# plp-cbot_2a.net
KiCad netlist of a schematic drawn in Altium Designer
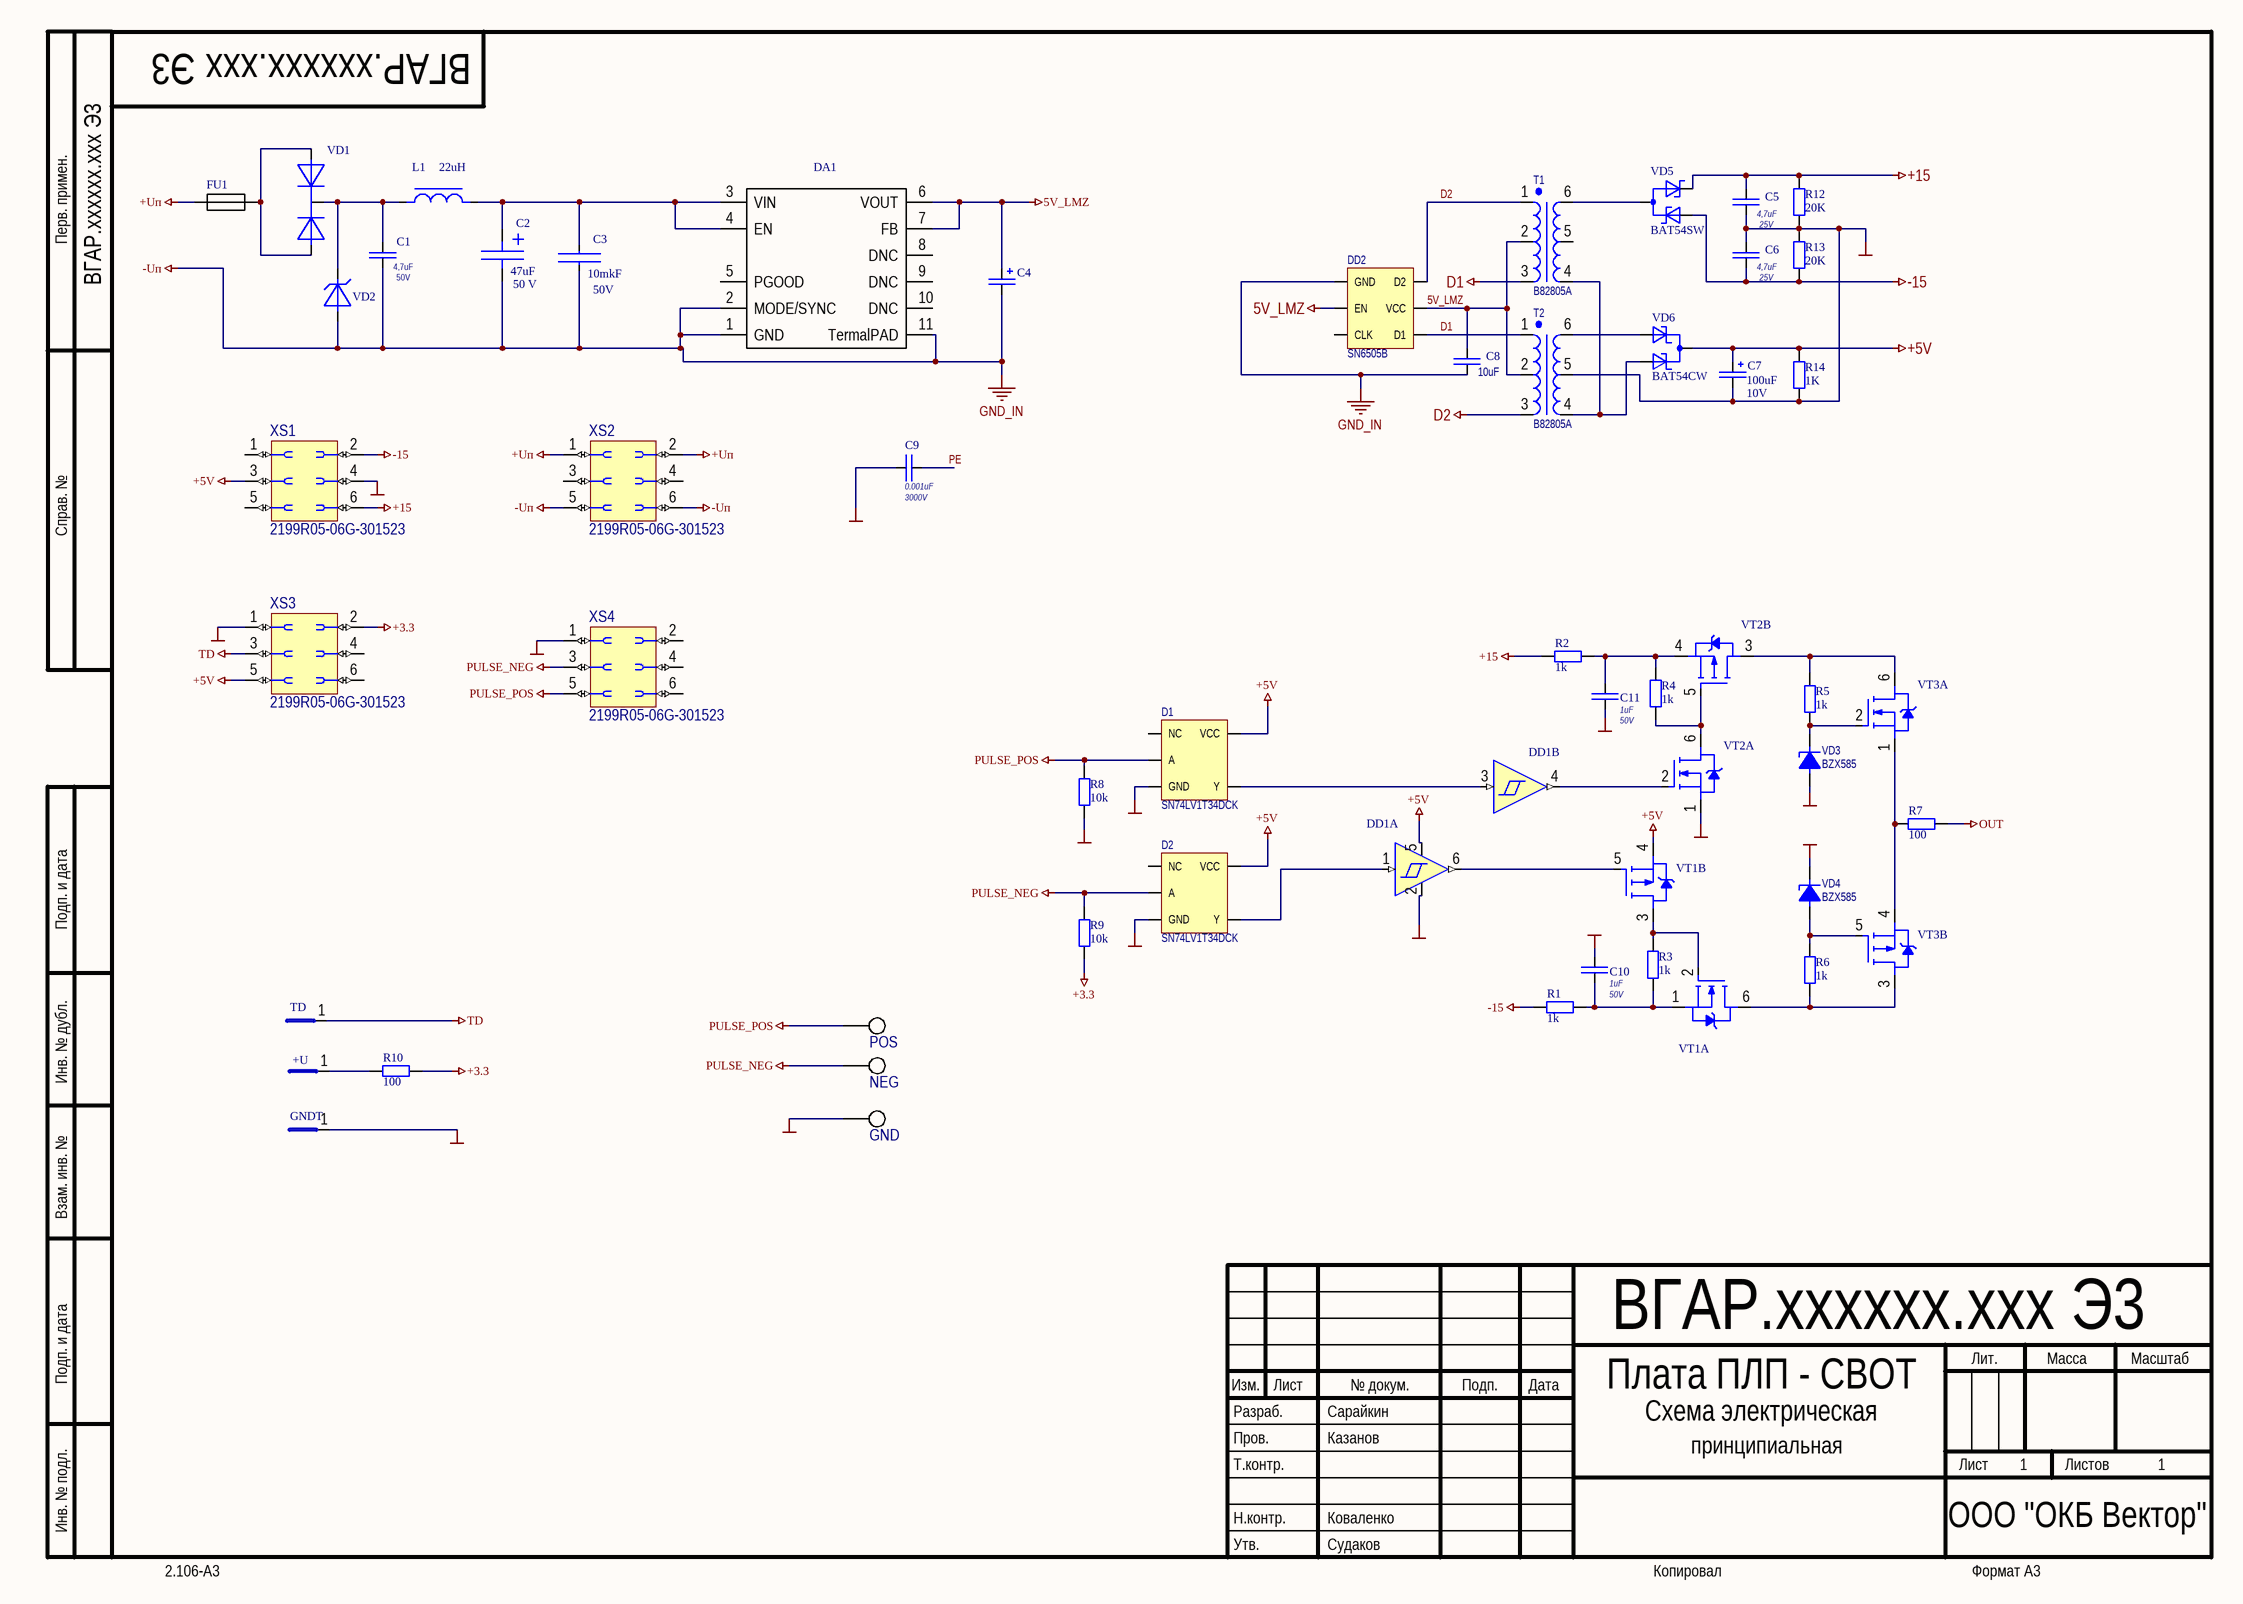
[diagram p0: plp-cbot_2a.SchDoc]

(export (version "E")
  (design (tool "Eeschema 10.0.6"))
  (components
    (comp (ref "+U")
      (value "smd_pin")
      (footprint "smd_pin")
      (libsource (lib "Board Level Debug Tools") (part "smd_pin"))
    )
    (comp (ref "C1")
      (value "4,7uF")
      (footprint "CAPC_0603(1608)X080L")
      (description "Конденсатор")
      (fields
        (field (name "MANUFACTURER") "Murata")
        (field (name "TOLERANCE") "±10%")
        (field (name "RATED DC VOLTAGE") "50V")
      )
      (libsource (lib "Chip Capacitor") (part "Capacitor Ceramic"))
    )
    (comp (ref "C2")
      (value "47uF")
      (footprint "CAPSM_D_M7878X54L")
      (description "Конденсатор")
      (fields
        (field (name "MANUFACTURER") "Panasonic")
        (field (name "TOLERANCE") "±20%")
        (field (name "RATED DC VOLTAGE") "50 V")
      )
      (libsource (lib "Panasonic Capacitor") (part "SMD 5.3XD6.3 ALUM 22uFx50V"))
    )
    (comp (ref "C3")
      (value "10mkF")
      (footprint "CAPC_1210(3225)X10L")
      (description "Capacitor Chip")
      (fields (field (name "ALTIUM_UNNAMED_1") "50V") (field (name "Comment") "CAPC_1210(3225)X10"))
      (libsource (lib "Yageo Chip Capacitor") (part "CAPC_1210(3225)X10"))
    )
    (comp (ref "C4")
      (value "~")
      (footprint "CAP_B3528X21N")
      (description "Конденсатор")
      (fields (field (name "MANUFACTURER") "Murata"))
      (libsource (lib "Chip Capacitor") (part "Capacitor Polarized"))
    )
    (comp (ref "C5")
      (value "4,7uF")
      (footprint "CAPC_0603(1608)X080L")
      (description "Конденсатор")
      (fields
        (field (name "MANUFACTURER") "Murata")
        (field (name "TOLERANCE") "±10%")
        (field (name "RATED DC VOLTAGE") "25V")
      )
      (libsource (lib "Chip Capacitor") (part "Capacitor Ceramic"))
    )
    (comp (ref "C6")
      (value "4,7uF")
      (footprint "CAPC_0603(1608)X080L")
      (description "Конденсатор")
      (fields
        (field (name "MANUFACTURER") "Murata")
        (field (name "TOLERANCE") "±10%")
        (field (name "RATED DC VOLTAGE") "25V")
      )
      (libsource (lib "Chip Capacitor") (part "Capacitor Ceramic"))
    )
    (comp (ref "C7")
      (value "100uF")
      (footprint "CAP_B3528X21N")
      (description "Конденсатор")
      (fields (field (name "MANUFACTURER") "Murata") (field (name "RATED DC VOLTAGE") "10V"))
      (libsource (lib "Chip Capacitor") (part "Capacitor Polarized"))
    )
    (comp (ref "C8")
      (value "10uF")
      (footprint "CAPC_0603(1608)X080L")
      (description "Конденсатор")
      (fields (field (name "MANUFACTURER") "Murata") (field (name "TOLERANCE") "±10%"))
      (libsource (lib "Chip Capacitor") (part "Capacitor Ceramic"))
    )
    (comp (ref "C9")
      (value "0.001uF")
      (footprint "CAPC_1812(4532)X16L")
      (description "Конденсатор")
      (fields
        (field (name "MANUFACTURER") "Murata")
        (field (name "PARTNUMBER") "0603 - 0,1 мкФ ± 10 % - 50 В - X7R")
        (field (name "RATED DC VOLTAGE") "3000V")
      )
      (libsource (lib "Chip Capacitor") (part "Capacitor Ceramic"))
    )
    (comp (ref "C10")
      (value "1uF")
      (footprint "CAPC_0603(1608)X080L")
      (description "Конденсатор")
      (fields
        (field (name "MANUFACTURER") "Murata")
        (field (name "PARTNUMBER") "GRM188R71C105KA12D - 0603 - 1 мкФ ± 10 % - 16 В - X7R")
        (field (name "RATED DC VOLTAGE") "50V")
      )
      (libsource (lib "Chip Capacitor") (part "0603 - X7R - 16V - 1uF"))
    )
    (comp (ref "C11")
      (value "1uF")
      (footprint "CAPC_0603(1608)X080L")
      (description "Конденсатор")
      (fields
        (field (name "MANUFACTURER") "Murata")
        (field (name "PARTNUMBER") "GRM188R71C105KA12D - 0603 - 1 мкФ ± 10 % - 16 В - X7R")
        (field (name "RATED DC VOLTAGE") "50V")
      )
      (libsource (lib "Chip Capacitor") (part "0603 - X7R - 16V - 1uF"))
    )
    (comp (ref "D1")
      (value "SN74LV1T34DCK")
      (footprint "SC70-5")
      (description "Single Buffer")
      (libsource (lib "ic-logic") (part "SN74LV1T34DCK"))
    )
    (comp (ref "D2")
      (value "SN74LV1T34DCK")
      (footprint "SC70-5")
      (description "Single Buffer")
      (libsource (lib "ic-logic") (part "SN74LV1T34DCK"))
    )
    (comp (ref "DA1")
      (value "LMZM23600")
      (footprint "MicroSIP")
      (description "Микросхема")
      (fields (field (name "MANUFACTURER") "Texas Instruments"))
      (libsource (lib "TI Power Mgt Switchmode Regulator") (part "LMZM23600"))
    )
    (comp (ref "DD1")
      (value "NC7WZ17P6X")
      (footprint "SC-70-6")
      (description "UHS Dual Buffer with Schmitt Trigger Inputs")
      (libsource (lib "Fairchild Logic") (part "NC7WZ17P6X"))
    )
    (comp (ref "DD2")
      (value "SN6505B")
      (footprint "SOT23-6")
      (description "Low-Noise 1-A Transformer Drivers for Isolated Power Supplies")
      (libsource (lib "ic-power-module") (part "SN6505A"))
    )
    (comp (ref "FU1")
      (value "MF-MSMF")
      (footprint "FU4532(1812)X06N")
      (description "Самовостанавливающийся предохранитель")
      (fields (field (name "MANUFACTURER") "Bourns") (field (name "PARTNUMBER") "MF-MSMF 010/60-2"))
      (libsource (lib "Bourns Chip Fuse") (part "MF-MSMF"))
    )
    (comp (ref "GND")
      (value "Testpoint_HS1mm")
      (footprint "TestPoint(1mm_HS)")
      (libsource (lib "connector") (part "Testpoint_HS1mm"))
    )
    (comp (ref "GNDT")
      (value "smd_pin")
      (footprint "smd_pin")
      (libsource (lib "Board Level Debug Tools") (part "smd_pin"))
    )
    (comp (ref "L1")
      (value "22uH")
      (footprint "CDRH4D28_INDP5050X28N")
      (fields (field (name "Comment") "CDRH4D28"))
      (libsource (lib "Sumida Power Inductor") (part "CDRH4D28"))
    )
    (comp (ref "NEG")
      (value "Testpoint_HS1mm")
      (footprint "TestPoint(1mm_HS)")
      (libsource (lib "connector") (part "Testpoint_HS1mm"))
    )
    (comp (ref "POS")
      (value "Testpoint_HS1mm")
      (footprint "TestPoint(1mm_HS)")
      (libsource (lib "connector") (part "Testpoint_HS1mm"))
    )
    (comp (ref "R1")
      (value "1k")
      (footprint "RESC1608(0603)X04L")
      (description "Резистор")
      (fields (field (name "MANUFACTURER") "Bourns") (field (name "POWER") "1/10 Вт"))
      (libsource (lib "") (part "R0603L_2"))
    )
    (comp (ref "R2")
      (value "1k")
      (footprint "RESC1608(0603)X04L")
      (description "Резистор")
      (fields (field (name "MANUFACTURER") "Bourns") (field (name "POWER") "1/10 Вт"))
      (libsource (lib "") (part "R0603L_2"))
    )
    (comp (ref "R3")
      (value "1k")
      (footprint "RESC1608(0603)X04L")
      (description "Резистор")
      (fields (field (name "MANUFACTURER") "Bourns") (field (name "POWER") "1/10 Вт"))
      (libsource (lib "") (part "R0603L_1"))
    )
    (comp (ref "R4")
      (value "1k")
      (footprint "RESC1608(0603)X04L")
      (description "Резистор")
      (fields (field (name "MANUFACTURER") "Bourns") (field (name "POWER") "1/10 Вт"))
      (libsource (lib "") (part "R0603L_1"))
    )
    (comp (ref "R5")
      (value "1k")
      (footprint "RESC1608(0603)X04L")
      (description "Резистор")
      (fields (field (name "MANUFACTURER") "Bourns") (field (name "POWER") "1/10 Вт"))
      (libsource (lib "Chip Resistor") (part "R0603L"))
    )
    (comp (ref "R6")
      (value "1k")
      (footprint "RESC1608(0603)X04L")
      (description "Резистор")
      (fields (field (name "MANUFACTURER") "Bourns") (field (name "POWER") "1/10 Вт"))
      (libsource (lib "Chip Resistor") (part "R0603L"))
    )
    (comp (ref "R7")
      (value "100")
      (footprint "RESC1608(0603)X04L")
      (description "Резистор")
      (fields (field (name "MANUFACTURER") "Bourns") (field (name "POWER") "1/10 Вт"))
      (libsource (lib "") (part "R0603L_3"))
    )
    (comp (ref "R8")
      (value "10k")
      (footprint "RESC1608(0603)X04L")
      (description "Резистор")
      (fields (field (name "MANUFACTURER") "Bourns") (field (name "POWER") "1/10 Вт"))
      (libsource (lib "") (part "R0603L_1"))
    )
    (comp (ref "R9")
      (value "10k")
      (footprint "RESC1608(0603)X04L")
      (description "Резистор")
      (fields (field (name "MANUFACTURER") "Bourns") (field (name "POWER") "1/10 Вт"))
      (libsource (lib "") (part "R0603L_1"))
    )
    (comp (ref "R10")
      (value "100")
      (footprint "RESC1608(0603)X04L")
      (description "Резистор")
      (fields (field (name "MANUFACTURER") "Bourns") (field (name "POWER") "1/10 Вт"))
      (libsource (lib "") (part "R0603L_3"))
    )
    (comp (ref "R12")
      (value "20K")
      (footprint "RESC1608(0603)X04L")
      (description "Резистор")
      (fields (field (name "MANUFACTURER") "Bourns") (field (name "POWER") "1/10 Вт"))
      (libsource (lib "") (part "R0603L_1"))
    )
    (comp (ref "R13")
      (value "20K")
      (footprint "RESC1608(0603)X04L")
      (description "Резистор")
      (fields (field (name "MANUFACTURER") "Bourns") (field (name "POWER") "1/10 Вт"))
      (libsource (lib "") (part "R0603L_1"))
    )
    (comp (ref "R14")
      (value "1K")
      (footprint "RESC1608(0603)X04L")
      (description "Резистор")
      (fields (field (name "MANUFACTURER") "Bourns") (field (name "POWER") "1/10 Вт"))
      (libsource (lib "") (part "R0603L_1"))
    )
    (comp (ref "T1")
      (value "B82805A")
      (footprint "B82805A")
      (description "SMT Push-Pull Transformers")
      (libsource (lib "transformer") (part "B82805A"))
    )
    (comp (ref "T2")
      (value "B82805A")
      (footprint "B82805A")
      (description "SMT Push-Pull Transformers")
      (libsource (lib "transformer") (part "B82805A"))
    )
    (comp (ref "TD")
      (value "smd_pin")
      (footprint "smd_pin")
      (libsource (lib "Board Level Debug Tools") (part "smd_pin"))
    )
    (comp (ref "VD1")
      (value "BAV70W")
      (footprint "SC-70")
      (description "Сборка диодная")
      (fields (field (name "MANUFACTURER") "NXP"))
      (libsource (lib "NXP Diodes") (part "BAV70W"))
    )
    (comp (ref "VD2")
      (value "SMBJ33A")
      (footprint "SMB")
      (description "TVS Диод")
      (fields
        (field (name "REPLACEMENTPART1PARTNUMBER") "PTVS33VP1UP")
        (field (name "MANUFACTURER") "ST Microelectronics")
      )
      (libsource (lib "ST Protection Diodes") (part "SMBJ33A"))
    )
    (comp (ref "VD3")
      (value "BZX585")
      (footprint "DIODE: SOD523")
      (description "Voltage regulator diodes")
      (libsource (lib "diode") (part "BZX585"))
    )
    (comp (ref "VD4")
      (value "BZX585")
      (footprint "DIODE: SOD523")
      (description "Voltage regulator diodes")
      (libsource (lib "diode") (part "BZX585"))
    )
    (comp (ref "VD5")
      (value "BAT54SW")
      (footprint "SC-70")
      (description "Сборка диодная")
      (fields (field (name "MANUFACTURER") "NXP") (field (name "REPLACEMENTPART1PARTNUMBER") "BAT54SWT1G"))
      (libsource (lib "NXP Diodes") (part "BAT54SW"))
    )
    (comp (ref "VD6")
      (value "BAT54CW")
      (footprint "SC-70")
      (description "Сборка диодная")
      (fields (field (name "MANUFACTURER") "NXP") (field (name "REPLACEMENTPART1PARTNUMBER") "BAT54CWT1G"))
      (libsource (lib "NXP Diodes") (part "BAT54CW"))
    )
    (comp (ref "VT1")
      (value "NX3008CBKS")
      (footprint "SC-70-6")
      (description "Сборка транзисторная")
      (fields (field (name "MANUFACTURER") "Fairchild Semiconductor") (field (name "PARTNUMBER") "BSS84AKS"))
      (libsource (lib "NXP Transistors") (part "NX3008CBKS"))
    )
    (comp (ref "VT2")
      (value "NX3008CBKS")
      (footprint "SC-70-6")
      (description "Сборка транзисторная")
      (fields (field (name "MANUFACTURER") "Fairchild Semiconductor") (field (name "PARTNUMBER") "BSS84AKS"))
      (libsource (lib "NXP Transistors") (part "NX3008CBKS"))
    )
    (comp (ref "VT3")
      (value "NX3008CBKS")
      (footprint "SC-70-6")
      (description "Сборка транзисторная")
      (fields (field (name "MANUFACTURER") "Fairchild Semiconductor") (field (name "PARTNUMBER") "BSS84AKS"))
      (libsource (lib "NXP Transistors") (part "NX3008CBKS"))
    )
    (comp (ref "XS1")
      (value "2199R05-06G-301523")
      (footprint "CON: PLL-6(2x3R1.27female)")
      (description "Step 1.27")
      (libsource (lib "connector") (part "2199R05-06G-301523In"))
    )
    (comp (ref "XS2")
      (value "2199R05-06G-301523")
      (footprint "CON: PLL-6(2x3R1.27female)")
      (description "Step 1.27")
      (libsource (lib "connector") (part "2199R05-06G-301523In"))
    )
    (comp (ref "XS3")
      (value "2199R05-06G-301523")
      (footprint "CON: PLL-6(2x3R1.27female)")
      (description "Step 1.27")
      (libsource (lib "connector") (part "2199R05-06G-301523In"))
    )
    (comp (ref "XS4")
      (value "2199R05-06G-301523")
      (footprint "CON: PLL-6(2x3R1.27female)")
      (description "Step 1.27")
      (libsource (lib "connector") (part "2199R05-06G-301523In"))
    )
  )
  (nets
    (net (code "1") (name "+3.3") (class "Default")
      (node (ref "R10") (pin "2") (pinfunction "2_2") (pintype "passive"))
      (node (ref "R9") (pin "1") (pinfunction "1_1") (pintype "passive"))
      (node (ref "XS3") (pin "2") (pinfunction "2_2") (pintype "bidirectional"))
    )
    (net (code "2") (name "+5V") (class "Default")
      (node (ref "C7") (pin "1") (pinfunction "1_1") (pintype "passive"))
      (node (ref "D1") (pin "5") (pinfunction "VCC_5") (pintype "passive"))
      (node (ref "D2") (pin "5") (pinfunction "VCC_5") (pintype "passive"))
      (node (ref "DD1") (pin "5") (pinfunction "Vdd_5") (pintype "passive"))
      (node (ref "R14") (pin "2") (pinfunction "2_2") (pintype "passive"))
      (node (ref "VD6") (pin "3") (pinfunction "OC_3") (pintype "passive"))
      (node (ref "VT1") (pin "4") (pinfunction "S2_4") (pintype "passive"))
      (node (ref "XS1") (pin "3") (pinfunction "3_3") (pintype "bidirectional"))
      (node (ref "XS3") (pin "5") (pinfunction "5_5") (pintype "bidirectional"))
    )
    (net (code "3") (name "+15") (class "Default")
      (node (ref "C5") (pin "2") (pinfunction "2_2") (pintype "passive"))
      (node (ref "R12") (pin "2") (pinfunction "2_2") (pintype "passive"))
      (node (ref "R2") (pin "2") (pinfunction "2_2") (pintype "passive"))
      (node (ref "VD5") (pin "2") (pinfunction "C_2") (pintype "passive"))
      (node (ref "XS1") (pin "6") (pinfunction "6_6") (pintype "bidirectional"))
    )
    (net (code "4") (name "+Uп") (class "Default")
      (node (ref "FU1") (pin "1") (pinfunction "1_1") (pintype "passive"))
      (node (ref "XS2") (pin "1") (pinfunction "1_1") (pintype "bidirectional"))
      (node (ref "XS2") (pin "2") (pinfunction "2_2") (pintype "bidirectional"))
    )
    (net (code "5") (name "-15") (class "Default")
      (node (ref "C6") (pin "1") (pinfunction "1_1") (pintype "passive"))
      (node (ref "R1") (pin "2") (pinfunction "2_2") (pintype "passive"))
      (node (ref "R13") (pin "1") (pinfunction "1_1") (pintype "passive"))
      (node (ref "VD5") (pin "1") (pinfunction "A_1") (pintype "passive"))
      (node (ref "XS1") (pin "2") (pinfunction "2_2") (pintype "bidirectional"))
    )
    (net (code "6") (name "-Uп") (class "Default")
      (node (ref "C1") (pin "1") (pinfunction "1_1") (pintype "passive"))
      (node (ref "C2") (pin "2") (pinfunction "2_2") (pintype "passive"))
      (node (ref "C3") (pin "1") (pinfunction "1_1") (pintype "passive"))
      (node (ref "C4") (pin "2") (pinfunction "2_2") (pintype "passive"))
      (node (ref "C8") (pin "1") (pinfunction "1_1") (pintype "passive"))
      (node (ref "DA1") (pin "1") (pinfunction "GND_1") (pintype "passive"))
      (node (ref "DA1") (pin "11") (pinfunction "TermalPAD_11") (pintype "passive"))
      (node (ref "DA1") (pin "2") (pinfunction "MODE/SYNC_2") (pintype "passive"))
      (node (ref "DD2") (pin "4") (pinfunction "GND_4") (pintype "passive"))
      (node (ref "VD2") (pin "2") (pinfunction "A_2") (pintype "passive"))
      (node (ref "XS2") (pin "5") (pinfunction "5_5") (pintype "bidirectional"))
      (node (ref "XS2") (pin "6") (pinfunction "6_6") (pintype "bidirectional"))
    )
    (net (code "7") (name "/PE") (class "Default")
      (node (ref "C9") (pin "2") (pinfunction "2_2") (pintype "passive"))
    )
    (net (code "8") (name "5V_LMZ") (class "Default")
      (node (ref "C4") (pin "1") (pinfunction "1_1") (pintype "passive"))
      (node (ref "C8") (pin "2") (pinfunction "2_2") (pintype "passive"))
      (node (ref "DA1") (pin "6") (pinfunction "VOUT_6") (pintype "passive"))
      (node (ref "DA1") (pin "7") (pinfunction "FB_7") (pintype "passive"))
      (node (ref "DD2") (pin "2") (pinfunction "VCC_2") (pintype "passive"))
      (node (ref "DD2") (pin "5") (pinfunction "EN_5") (pintype "passive"))
      (node (ref "T1") (pin "2") (pinfunction "2_2") (pintype "passive"))
      (node (ref "T2") (pin "2") (pinfunction "2_2") (pintype "passive"))
    )
    (net (code "9") (name "D1") (class "Default")
      (node (ref "DD2") (pin "1") (pinfunction "D1_1") (pintype "passive"))
      (node (ref "T1") (pin "3") (pinfunction "3_3") (pintype "passive"))
      (node (ref "T2") (pin "1") (pinfunction "1_1") (pintype "passive"))
    )
    (net (code "10") (name "D2") (class "Default")
      (node (ref "DD2") (pin "3") (pinfunction "D2_3") (pintype "passive"))
      (node (ref "T1") (pin "1") (pinfunction "1_1") (pintype "passive"))
      (node (ref "T2") (pin "3") (pinfunction "3_3") (pintype "passive"))
    )
    (net (code "11") (name "GND") (class "Default")
      (node (ref "C10") (pin "2") (pinfunction "2_2") (pintype "passive"))
      (node (ref "C11") (pin "1") (pinfunction "1_1") (pintype "passive"))
      (node (ref "C5") (pin "1") (pinfunction "1_1") (pintype "passive"))
      (node (ref "C6") (pin "2") (pinfunction "2_2") (pintype "passive"))
      (node (ref "C7") (pin "2") (pinfunction "2_2") (pintype "passive"))
      (node (ref "C9") (pin "1") (pinfunction "1_1") (pintype "passive"))
      (node (ref "D1") (pin "3") (pinfunction "GND_3") (pintype "passive"))
      (node (ref "D2") (pin "3") (pinfunction "GND_3") (pintype "passive"))
      (node (ref "DD1") (pin "2") (pinfunction "GND_2") (pintype "passive"))
      (node (ref "GND") (pin "1") (pinfunction "1_1") (pintype "passive"))
      (node (ref "GNDT") (pin "1") (pinfunction "0_1") (pintype "passive"))
      (node (ref "R12") (pin "1") (pinfunction "1_1") (pintype "passive"))
      (node (ref "R13") (pin "2") (pinfunction "2_2") (pintype "passive"))
      (node (ref "R14") (pin "1") (pinfunction "1_1") (pintype "passive"))
      (node (ref "R8") (pin "1") (pinfunction "1_1") (pintype "passive"))
      (node (ref "T2") (pin "5") (pinfunction "5_5") (pintype "passive"))
      (node (ref "VD3") (pin "1") (pinfunction "2_1") (pintype "passive"))
      (node (ref "VD4") (pin "2") (pinfunction "1_2") (pintype "passive"))
      (node (ref "VT2") (pin "1") (pinfunction "S1_1") (pintype "passive"))
      (node (ref "XS1") (pin "4") (pinfunction "4_4") (pintype "bidirectional"))
      (node (ref "XS3") (pin "1") (pinfunction "1_1") (pintype "bidirectional"))
      (node (ref "XS4") (pin "1") (pinfunction "1_1") (pintype "bidirectional"))
    )
    (net (code "12") (name "Net-(+U-0)") (class "Default")
      (node (ref "+U") (pin "1") (pinfunction "0_1") (pintype "passive"))
      (node (ref "R10") (pin "1") (pinfunction "1_1") (pintype "passive"))
    )
    (net (code "13") (name "Net-(D1-Y)") (class "Default")
      (node (ref "D1") (pin "4") (pinfunction "Y_4") (pintype "passive"))
      (node (ref "DD1") (pin "3") (pinfunction "A2_3") (pintype "input"))
    )
    (net (code "14") (name "Net-(D2-Y)") (class "Default")
      (node (ref "D2") (pin "4") (pinfunction "Y_4") (pintype "passive"))
      (node (ref "DD1") (pin "1") (pinfunction "A1_1") (pintype "input"))
    )
    (net (code "15") (name "Net-(DA1-EN)") (class "Default")
      (node (ref "C2") (pin "1") (pinfunction "1_1") (pintype "passive"))
      (node (ref "C3") (pin "2") (pinfunction "2_2") (pintype "passive"))
      (node (ref "DA1") (pin "3") (pinfunction "VIN_3") (pintype "passive"))
      (node (ref "DA1") (pin "4") (pinfunction "EN_4") (pintype "passive"))
      (node (ref "L1") (pin "2") (pinfunction "2_2") (pintype "passive"))
    )
    (net (code "16") (name "Net-(DD1A-Y1)") (class "Default")
      (node (ref "DD1") (pin "6") (pinfunction "Y1_6") (pintype "output"))
      (node (ref "VT1") (pin "5") (pinfunction "G2_5") (pintype "passive"))
    )
    (net (code "17") (name "Net-(DD1B-Y2)") (class "Default")
      (node (ref "DD1") (pin "4") (pinfunction "Y2_4") (pintype "output"))
      (node (ref "VT2") (pin "2") (pinfunction "G1_2") (pintype "passive"))
    )
    (net (code "18") (name "Net-(FU1-Pad2)") (class "Default")
      (node (ref "FU1") (pin "2") (pinfunction "2_2") (pintype "passive"))
      (node (ref "VD1") (pin "1") (pinfunction "A_1") (pintype "passive"))
      (node (ref "VD1") (pin "2") (pinfunction "A_2") (pintype "passive"))
    )
    (net (code "19") (name "Net-(T1-Pad4)") (class "Default")
      (node (ref "T1") (pin "4") (pinfunction "4_4") (pintype "passive"))
      (node (ref "T2") (pin "4") (pinfunction "4_4") (pintype "passive"))
      (node (ref "VD6") (pin "2") (pinfunction "A_2") (pintype "passive"))
    )
    (net (code "20") (name "Net-(T2-Pad6)") (class "Default")
      (node (ref "T2") (pin "6") (pinfunction "6_6") (pintype "passive"))
      (node (ref "VD6") (pin "1") (pinfunction "A_1") (pintype "passive"))
    )
    (net (code "21") (name "Net-(VD1-OC)") (class "Default")
      (node (ref "C1") (pin "2") (pinfunction "2_2") (pintype "passive"))
      (node (ref "L1") (pin "1") (pinfunction "1_1") (pintype "passive"))
      (node (ref "VD1") (pin "3") (pinfunction "OC_3") (pintype "passive"))
      (node (ref "VD2") (pin "1") (pinfunction "C_1") (pintype "passive"))
    )
    (net (code "22") (name "Net-(VD3-1)") (class "Default")
      (node (ref "R5") (pin "2") (pinfunction "2_2") (pintype "passive"))
      (node (ref "VD3") (pin "2") (pinfunction "1_2") (pintype "passive"))
      (node (ref "VT3") (pin "2") (pinfunction "G1_2") (pintype "passive"))
    )
    (net (code "23") (name "Net-(VD4-2)") (class "Default")
      (node (ref "R6") (pin "1") (pinfunction "1_1") (pintype "passive"))
      (node (ref "VD4") (pin "1") (pinfunction "2_1") (pintype "passive"))
      (node (ref "VT3") (pin "5") (pinfunction "G2_5") (pintype "passive"))
    )
    (net (code "24") (name "Net-(VD5-OAC)") (class "Default")
      (node (ref "T1") (pin "6") (pinfunction "6_6") (pintype "passive"))
      (node (ref "VD5") (pin "3") (pinfunction "OAC_3") (pintype "passive"))
    )
    (net (code "25") (name "Net-(VT1A-D1)") (class "Default")
      (node (ref "R6") (pin "2") (pinfunction "2_2") (pintype "passive"))
      (node (ref "VT1") (pin "6") (pinfunction "D1_6") (pintype "passive"))
      (node (ref "VT3") (pin "3") (pinfunction "D2_3") (pintype "passive"))
    )
    (net (code "26") (name "Net-(VT1A-G1)") (class "Default")
      (node (ref "R3") (pin "2") (pinfunction "2_2") (pintype "passive"))
      (node (ref "VT1") (pin "2") (pinfunction "G1_2") (pintype "passive"))
      (node (ref "VT1") (pin "3") (pinfunction "D2_3") (pintype "passive"))
    )
    (net (code "27") (name "Net-(VT1A-S1)") (class "Default")
      (node (ref "C10") (pin "1") (pinfunction "1_1") (pintype "passive"))
      (node (ref "R1") (pin "1") (pinfunction "1_1") (pintype "passive"))
      (node (ref "R3") (pin "1") (pinfunction "1_1") (pintype "passive"))
      (node (ref "VT1") (pin "1") (pinfunction "S1_1") (pintype "passive"))
    )
    (net (code "28") (name "Net-(VT2A-D1)") (class "Default")
      (node (ref "R4") (pin "1") (pinfunction "1_1") (pintype "passive"))
      (node (ref "VT2") (pin "5") (pinfunction "G2_5") (pintype "passive"))
      (node (ref "VT2") (pin "6") (pinfunction "D1_6") (pintype "passive"))
    )
    (net (code "29") (name "Net-(VT2B-D2)") (class "Default")
      (node (ref "R5") (pin "1") (pinfunction "1_1") (pintype "passive"))
      (node (ref "VT2") (pin "3") (pinfunction "D2_3") (pintype "passive"))
      (node (ref "VT3") (pin "6") (pinfunction "D1_6") (pintype "passive"))
    )
    (net (code "30") (name "Net-(VT2B-S2)") (class "Default")
      (node (ref "C11") (pin "2") (pinfunction "2_2") (pintype "passive"))
      (node (ref "R2") (pin "1") (pinfunction "1_1") (pintype "passive"))
      (node (ref "R4") (pin "2") (pinfunction "2_2") (pintype "passive"))
      (node (ref "VT2") (pin "4") (pinfunction "S2_4") (pintype "passive"))
    )
    (net (code "31") (name "Net-(VT3A-S1)") (class "Default")
      (node (ref "R7") (pin "1") (pinfunction "1_1") (pintype "passive"))
      (node (ref "VT3") (pin "1") (pinfunction "S1_1") (pintype "passive"))
      (node (ref "VT3") (pin "4") (pinfunction "S2_4") (pintype "passive"))
    )
    (net (code "32") (name "OUT") (class "Default")
      (node (ref "R7") (pin "2") (pinfunction "2_2") (pintype "passive"))
    )
    (net (code "33") (name "PULSE_NEG") (class "Default")
      (node (ref "D2") (pin "2") (pinfunction "A_2") (pintype "passive"))
      (node (ref "NEG") (pin "1") (pinfunction "1_1") (pintype "passive"))
      (node (ref "R9") (pin "2") (pinfunction "2_2") (pintype "passive"))
      (node (ref "XS4") (pin "3") (pinfunction "3_3") (pintype "bidirectional"))
    )
    (net (code "34") (name "PULSE_POS") (class "Default")
      (node (ref "D1") (pin "2") (pinfunction "A_2") (pintype "passive"))
      (node (ref "POS") (pin "1") (pinfunction "1_1") (pintype "passive"))
      (node (ref "R8") (pin "2") (pinfunction "2_2") (pintype "passive"))
      (node (ref "XS4") (pin "5") (pinfunction "5_5") (pintype "bidirectional"))
    )
    (net (code "35") (name "TD") (class "Default")
      (node (ref "TD") (pin "1") (pinfunction "0_1") (pintype "passive"))
      (node (ref "XS3") (pin "3") (pinfunction "3_3") (pintype "bidirectional"))
    )
    (net (code "36") (name "unconnected-(D1-NC-Pad1)") (class "Default")
      (node (ref "D1") (pin "1") (pinfunction "NC_1") (pintype "passive"))
    )
    (net (code "37") (name "unconnected-(D2-NC-Pad1)") (class "Default")
      (node (ref "D2") (pin "1") (pinfunction "NC_1") (pintype "passive"))
    )
    (net (code "38") (name "unconnected-(DA1-DNC-Pad8)") (class "Default")
      (node (ref "DA1") (pin "8") (pinfunction "DNC_8") (pintype "passive"))
    )
    (net (code "39") (name "unconnected-(DA1-DNC-Pad9)") (class "Default")
      (node (ref "DA1") (pin "9") (pinfunction "DNC_9") (pintype "passive"))
    )
    (net (code "40") (name "unconnected-(DA1-DNC-Pad10)") (class "Default")
      (node (ref "DA1") (pin "10") (pinfunction "DNC_10") (pintype "passive"))
    )
    (net (code "41") (name "unconnected-(DA1-PGOOD-Pad5)") (class "Default")
      (node (ref "DA1") (pin "5") (pinfunction "PGOOD_5") (pintype "passive"))
    )
    (net (code "42") (name "unconnected-(DD2-CLK-Pad6)") (class "Default")
      (node (ref "DD2") (pin "6") (pinfunction "CLK_6") (pintype "passive"))
    )
    (net (code "43") (name "unconnected-(T1-Pad5)") (class "Default")
      (node (ref "T1") (pin "5") (pinfunction "5_5") (pintype "passive"))
    )
    (net (code "44") (name "unconnected-(XS1-Pad1)") (class "Default")
      (node (ref "XS1") (pin "1") (pinfunction "1_1") (pintype "bidirectional"))
    )
    (net (code "45") (name "unconnected-(XS1-Pad5)") (class "Default")
      (node (ref "XS1") (pin "5") (pinfunction "5_5") (pintype "bidirectional"))
    )
    (net (code "46") (name "unconnected-(XS2-Pad3)") (class "Default")
      (node (ref "XS2") (pin "3") (pinfunction "3_3") (pintype "bidirectional"))
    )
    (net (code "47") (name "unconnected-(XS2-Pad4)") (class "Default")
      (node (ref "XS2") (pin "4") (pinfunction "4_4") (pintype "bidirectional"))
    )
    (net (code "48") (name "unconnected-(XS3-Pad4)") (class "Default")
      (node (ref "XS3") (pin "4") (pinfunction "4_4") (pintype "bidirectional"))
    )
    (net (code "49") (name "unconnected-(XS3-Pad6)") (class "Default")
      (node (ref "XS3") (pin "6") (pinfunction "6_6") (pintype "bidirectional"))
    )
    (net (code "50") (name "unconnected-(XS4-Pad2)") (class "Default")
      (node (ref "XS4") (pin "2") (pinfunction "2_2") (pintype "bidirectional"))
    )
    (net (code "51") (name "unconnected-(XS4-Pad4)") (class "Default")
      (node (ref "XS4") (pin "4") (pinfunction "4_4") (pintype "bidirectional"))
    )
    (net (code "52") (name "unconnected-(XS4-Pad6)") (class "Default")
      (node (ref "XS4") (pin "6") (pinfunction "6_6") (pintype "bidirectional"))
    )
  )
)
